# table4.net
KiCad netlist of a schematic drawn in EasyEDA
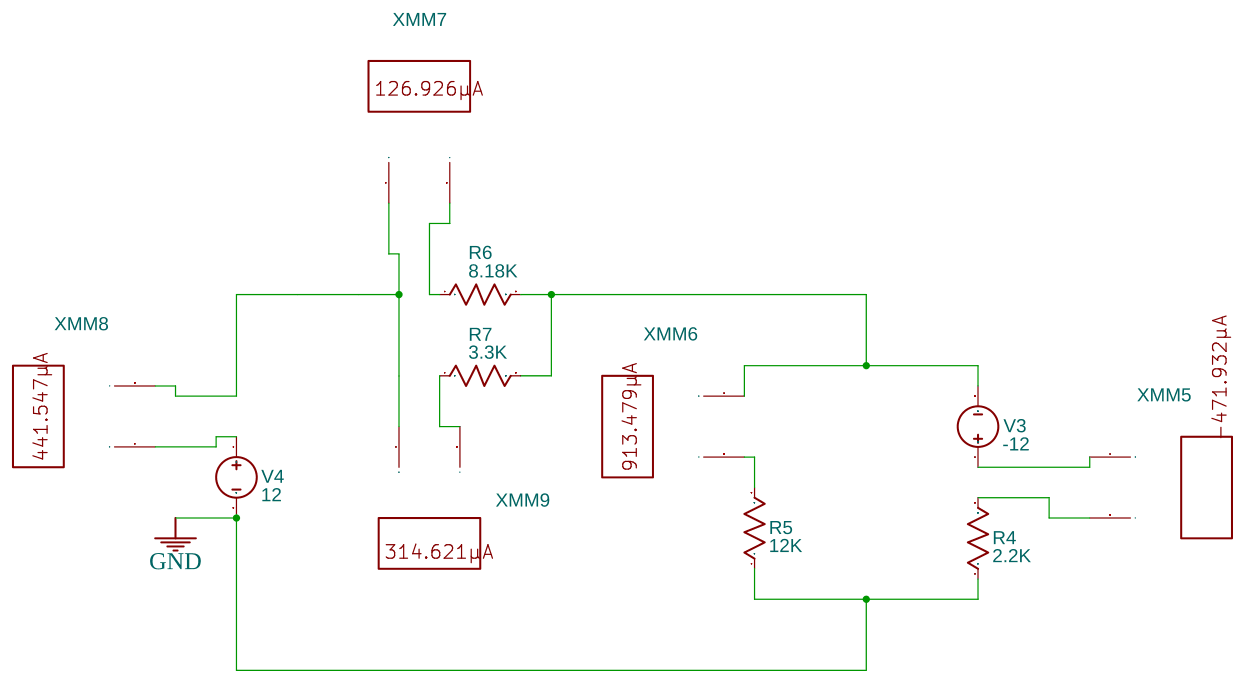
[diagram p0: schematic sheet]

(export (version "E")
  (design (tool "Eeschema 10.0.6"))
  (components
    (comp (ref "R4") (value "2.2K") (libsource (lib "") (part "Resistor_US_1")))
    (comp (ref "R5") (value "12K") (libsource (lib "") (part "Resistor_US_1")))
    (comp (ref "R6") (value "8.18K") (libsource (lib "") (part "Resistor_US")))
    (comp (ref "R7") (value "3.3K") (libsource (lib "") (part "Resistor_US")))
    (comp (ref "V3") (value "-12") (libsource (lib "") (part "VDC_1")))
    (comp (ref "V4") (value "12") (libsource (lib "") (part "VDC")))
    (comp (ref "XMM5") (value "Multimeter") (libsource (lib "") (part "MULTIMETER_1")))
    (comp (ref "XMM6") (value "Multimeter") (libsource (lib "") (part "MULTIMETER_4")))
    (comp (ref "XMM7") (value "Multimeter") (libsource (lib "") (part "MULTIMETER_3")))
    (comp (ref "XMM8") (value "Multimeter") (libsource (lib "") (part "MULTIMETER_2")))
    (comp (ref "XMM9") (value "Multimeter") (libsource (lib "") (part "MULTIMETER")))
  )
  (nets
    (net (code "1") (name "GND") (class "Default")
      (node (ref "R4") (pin "1") (pinfunction "1_1") (pintype "unspecified"))
      (node (ref "R5") (pin "1") (pinfunction "1_1") (pintype "unspecified"))
      (node (ref "V4") (pin "2") (pinfunction "2_2") (pintype "unspecified"))
    )
    (net (code "2") (name "Net-(XMM5-+)") (class "Default")
      (node (ref "V3") (pin "1") (pinfunction "1_1") (pintype "unspecified"))
      (node (ref "XMM5") (pin "1") (pinfunction "+_1") (pintype "unspecified"))
    )
    (net (code "3") (name "Net-(XMM5-I)") (class "Default")
      (node (ref "R4") (pin "2") (pinfunction "2_2") (pintype "unspecified"))
      (node (ref "XMM5") (pin "2") (pinfunction "I_2") (pintype "unspecified"))
    )
    (net (code "4") (name "Net-(XMM6-+)") (class "Default")
      (node (ref "R6") (pin "2") (pinfunction "2_2") (pintype "unspecified"))
      (node (ref "R7") (pin "2") (pinfunction "2_2") (pintype "unspecified"))
      (node (ref "V3") (pin "2") (pinfunction "2_2") (pintype "unspecified"))
      (node (ref "XMM6") (pin "1") (pinfunction "+_1") (pintype "unspecified"))
    )
    (net (code "5") (name "Net-(XMM6-I)") (class "Default")
      (node (ref "R5") (pin "2") (pinfunction "2_2") (pintype "unspecified"))
      (node (ref "XMM6") (pin "2") (pinfunction "I_2") (pintype "unspecified"))
    )
    (net (code "6") (name "Net-(XMM7-+)") (class "Default")
      (node (ref "XMM7") (pin "1") (pinfunction "+_1") (pintype "unspecified"))
      (node (ref "XMM8") (pin "2") (pinfunction "I_2") (pintype "unspecified"))
      (node (ref "XMM9") (pin "1") (pinfunction "+_1") (pintype "unspecified"))
    )
    (net (code "7") (name "Net-(XMM7-I)") (class "Default")
      (node (ref "R6") (pin "1") (pinfunction "1_1") (pintype "unspecified"))
      (node (ref "XMM7") (pin "2") (pinfunction "I_2") (pintype "unspecified"))
    )
    (net (code "8") (name "Net-(XMM8-+)") (class "Default")
      (node (ref "V4") (pin "1") (pinfunction "1_1") (pintype "unspecified"))
      (node (ref "XMM8") (pin "1") (pinfunction "+_1") (pintype "unspecified"))
    )
    (net (code "9") (name "Net-(XMM9-I)") (class "Default")
      (node (ref "R7") (pin "1") (pinfunction "1_1") (pintype "unspecified"))
      (node (ref "XMM9") (pin "2") (pinfunction "I_2") (pintype "unspecified"))
    )
  )
)
